# Sheet1.net
KiCad netlist of a schematic drawn in Altium Designer
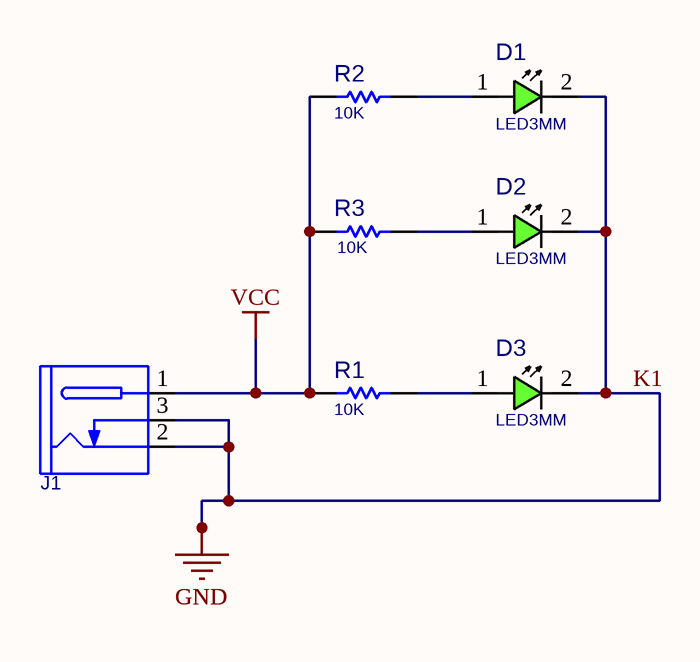
[diagram p0: Sheet1.SchDoc]

(export (version "E")
  (design (tool "Eeschema 10.0.6"))
  (components
    (comp (ref "D1")
      (value "LED3MM")
      (footprint "LED3MM")
      (description "LED, THD, 3MM, GREEN")
      (fields (field (name "MANF") "MANF") (field (name "MANF_P#") "MANF_PART#"))
      (libsource (lib "led(diode)") (part "LED_THD_3MM"))
    )
    (comp (ref "D2")
      (value "LED3MM")
      (footprint "LED3MM")
      (description "LED, THD, 3MM, GREEN")
      (fields (field (name "MANF") "MANF") (field (name "MANF_P#") "MANF_PART#"))
      (libsource (lib "led(diode)") (part "LED_THD_3MM"))
    )
    (comp (ref "D3")
      (value "LED3MM")
      (footprint "LED3MM")
      (description "LED, THD, 3MM, GREEN")
      (fields (field (name "MANF") "MANF") (field (name "MANF_P#") "MANF_PART#"))
      (libsource (lib "led(diode)") (part "LED_THD_3MM"))
    )
    (comp (ref "J1")
      (value "DC_POWER_JACK")
      (footprint "JAC_PWR1")
      (description "CONN, PWR JACK DC, PLUG DIAM 1.0MM RA THD")
      (fields (field (name "MANF") "CUI STACK") (field (name "MANF_P#") "PJ-031CH, PJ-031C"))
      (libsource (lib "conn_powerJack") (part "CONN_PWR_JACKR1"))
    )
    (comp (ref "R1")
      (value "10K")
      (footprint "R025W_AX04")
      (description "RESISTOR, THD")
      (fields (field (name "MANF_P#") "RK73H1ETTP4701F") (field (name "MANF") "KOA SPEER"))
      (libsource (lib "passive_thd") (part "RES_THD"))
    )
    (comp (ref "R2")
      (value "10K")
      (footprint "R025W_AX04")
      (description "RESISTOR, THD")
      (fields (field (name "MANF_P#") "RK73H1ETTP4701F") (field (name "MANF") "KOA SPEER"))
      (libsource (lib "passive_thd") (part "RES_THD"))
    )
    (comp (ref "R3")
      (value "10K")
      (footprint "R025W_AX04")
      (description "RESISTOR, THD")
      (fields (field (name "MANF_P#") "RK73H1ETTP4701F") (field (name "MANF") "KOA SPEER"))
      (libsource (lib "passive_thd") (part "RES_THD"))
    )
  )
  (nets
    (net (code "1") (name "GND") (class "Default")
      (node (ref "D1") (pin "2") (pinfunction "CATHODE_2") (pintype "passive"))
      (node (ref "D2") (pin "2") (pinfunction "CATHODE_2") (pintype "passive"))
      (node (ref "D3") (pin "2") (pinfunction "CATHODE_2") (pintype "passive"))
      (node (ref "J1") (pin "2") (pinfunction "SLEEVE_2") (pintype "power_in"))
      (node (ref "J1") (pin "3") (pinfunction "INSERTION_DET_3") (pintype "power_in"))
    )
    (net (code "2") (name "Net-(D1-ANODE)") (class "Default")
      (node (ref "D1") (pin "1") (pinfunction "ANODE_1") (pintype "passive"))
      (node (ref "R2") (pin "2") (pinfunction "2_2") (pintype "passive"))
    )
    (net (code "3") (name "Net-(D2-ANODE)") (class "Default")
      (node (ref "D2") (pin "1") (pinfunction "ANODE_1") (pintype "passive"))
      (node (ref "R3") (pin "2") (pinfunction "2_2") (pintype "passive"))
    )
    (net (code "4") (name "Net-(D3-ANODE)") (class "Default")
      (node (ref "D3") (pin "1") (pinfunction "ANODE_1") (pintype "passive"))
      (node (ref "R1") (pin "2") (pinfunction "2_2") (pintype "passive"))
    )
    (net (code "5") (name "VCC") (class "Default")
      (node (ref "J1") (pin "1") (pinfunction "TIP_1") (pintype "power_in"))
      (node (ref "R1") (pin "1") (pinfunction "1_1") (pintype "passive"))
      (node (ref "R2") (pin "1") (pinfunction "1_1") (pintype "passive"))
      (node (ref "R3") (pin "1") (pinfunction "1_1") (pintype "passive"))
    )
  )
)
